# LR_EVM.net
KiCad netlist of a schematic drawn in Altium Designer
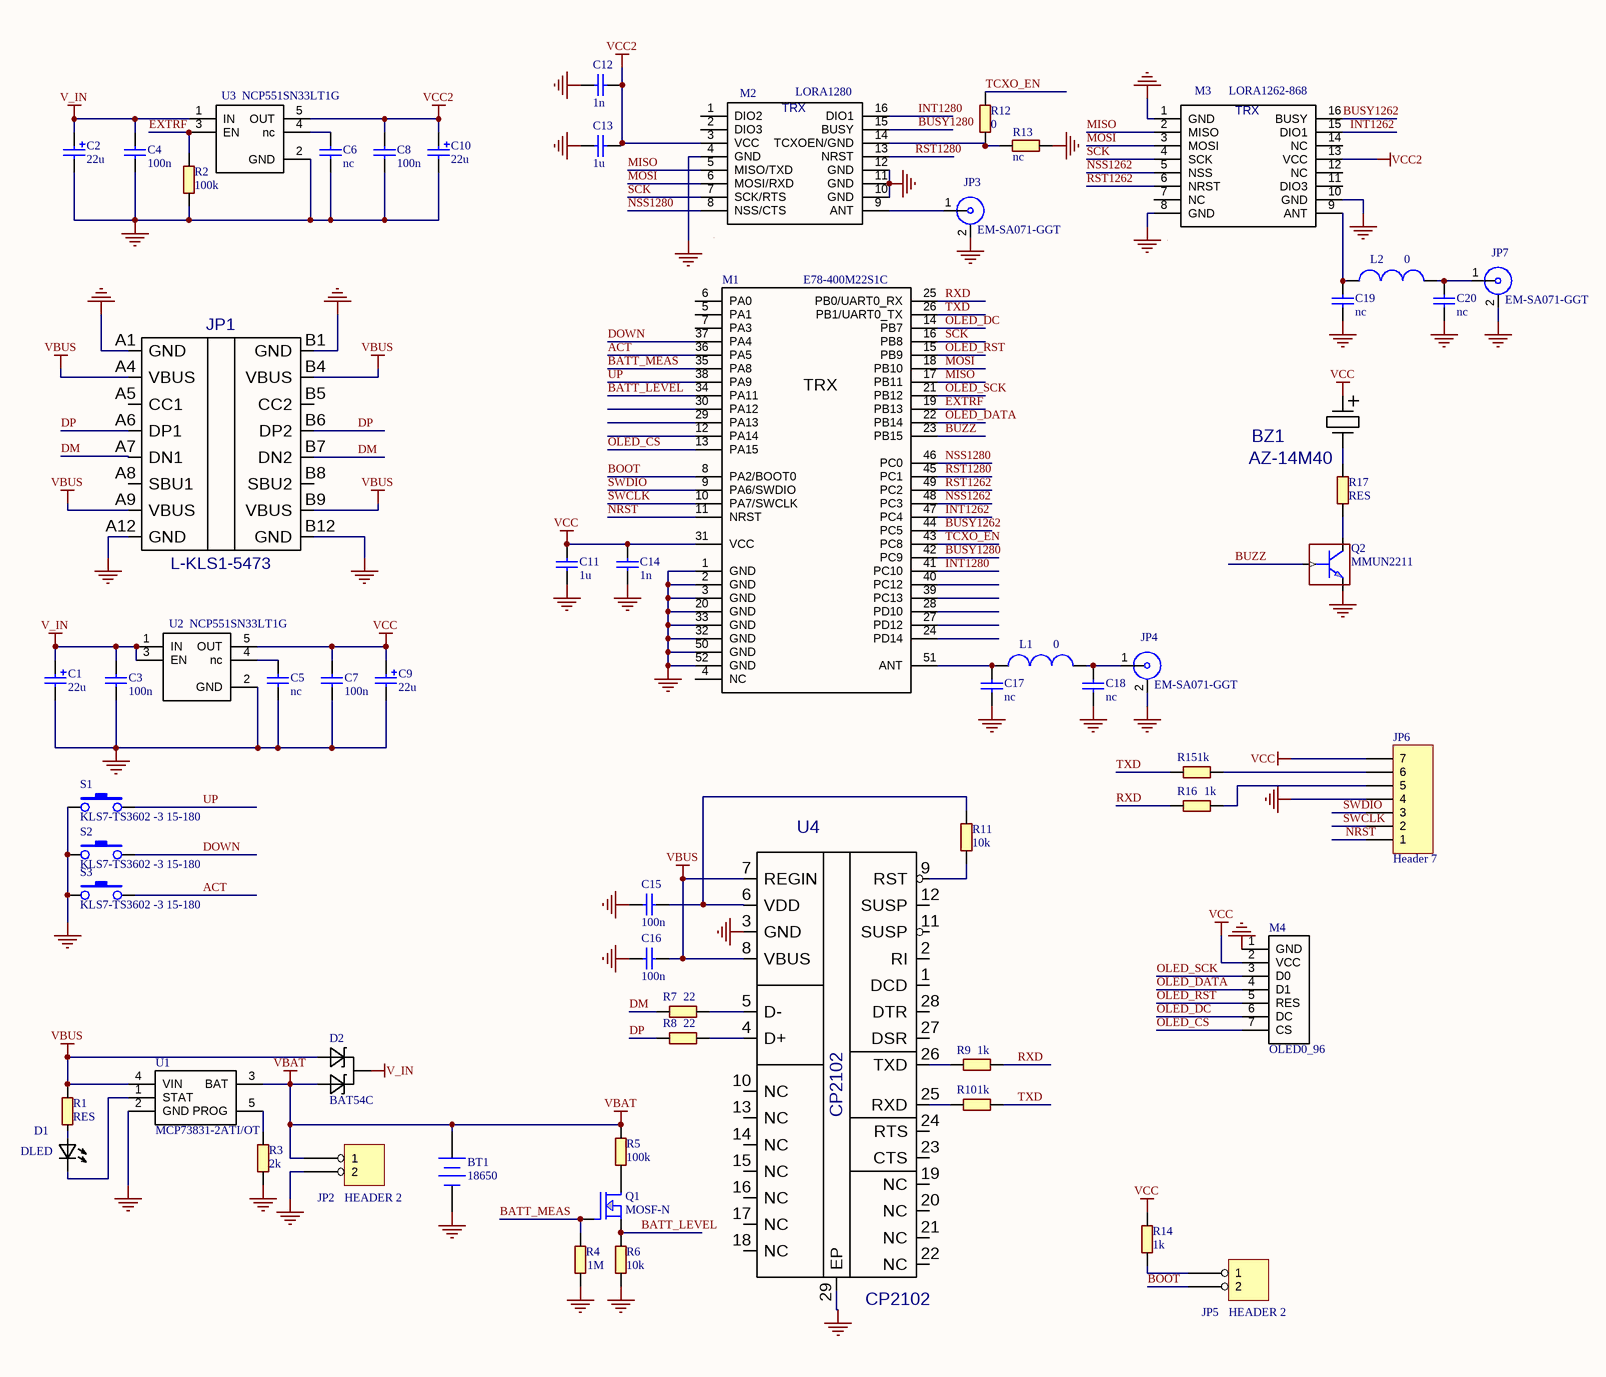
[diagram p0: LR_EVM.SchDoc]

(export (version "E")
  (design (tool "Eeschema 10.0.6"))
  (components
    (comp (ref "BT1")
      (value "18650")
      (footprint "18650")
      (description "Multicell Battery")
      (fields (field (name "PUBLISHER") "Altium Limited"))
      (libsource (lib "zucker") (part "Battery"))
    )
    (comp (ref "BZ1")
      (value "AZ-14M40")
      (footprint "AZ-14M40")
      (libsource (lib "zucker") (part "BUZ-AZ-14M40"))
    )
    (comp (ref "C1")
      (value "22u")
      (footprint "C_TANTAL_A")
      (fields (field (name "VOLTAGE") "16V"))
      (libsource (lib "Passive") (part "CAPP"))
    )
    (comp (ref "C2")
      (value "22u")
      (footprint "C_TANTAL_A")
      (fields (field (name "VOLTAGE") "16V"))
      (libsource (lib "Passive") (part "CAPP"))
    )
    (comp (ref "C3")
      (value "100n")
      (footprint "C-0603")
      (fields (field (name "VOLTAGE") "50V"))
      (libsource (lib "Passive") (part "CAPN"))
    )
    (comp (ref "C4")
      (value "100n")
      (footprint "C-0603")
      (fields (field (name "VOLTAGE") "50V"))
      (libsource (lib "Passive") (part "CAPN"))
    )
    (comp (ref "C5")
      (value "nc")
      (footprint "C-0603")
      (fields (field (name "VOLTAGE") "50V"))
      (libsource (lib "Passive") (part "CAPN"))
    )
    (comp (ref "C6")
      (value "nc")
      (footprint "C-0603")
      (fields (field (name "VOLTAGE") "50V"))
      (libsource (lib "Passive") (part "CAPN"))
    )
    (comp (ref "C7")
      (value "100n")
      (footprint "C-0603")
      (fields (field (name "VOLTAGE") "50V"))
      (libsource (lib "Passive") (part "CAPN"))
    )
    (comp (ref "C8")
      (value "100n")
      (footprint "C-0603")
      (fields (field (name "VOLTAGE") "50V"))
      (libsource (lib "Passive") (part "CAPN"))
    )
    (comp (ref "C9")
      (value "22u")
      (footprint "C_TANTAL_A")
      (fields (field (name "VOLTAGE") "16V"))
      (libsource (lib "Passive") (part "CAPP"))
    )
    (comp (ref "C10")
      (value "22u")
      (footprint "C_TANTAL_A")
      (fields (field (name "VOLTAGE") "16V"))
      (libsource (lib "Passive") (part "CAPP"))
    )
    (comp (ref "C11")
      (value "1u")
      (footprint "C-0603")
      (fields (field (name "VOLTAGE") "50V"))
      (libsource (lib "Passive") (part "CAPN"))
    )
    (comp (ref "C12")
      (value "1n")
      (footprint "C-0603")
      (fields (field (name "VOLTAGE") "50V"))
      (libsource (lib "Passive") (part "CAPN"))
    )
    (comp (ref "C13")
      (value "1u")
      (footprint "C-0603")
      (fields (field (name "VOLTAGE") "50V"))
      (libsource (lib "Passive") (part "CAPN"))
    )
    (comp (ref "C14")
      (value "1n")
      (footprint "C-0603")
      (fields (field (name "VOLTAGE") "50V"))
      (libsource (lib "Passive") (part "CAPN"))
    )
    (comp (ref "C15")
      (value "100n")
      (footprint "C-0603")
      (fields (field (name "VOLTAGE") "50V"))
      (libsource (lib "Passive") (part "CAPN"))
    )
    (comp (ref "C16")
      (value "100n")
      (footprint "C-0603")
      (fields (field (name "VOLTAGE") "50V"))
      (libsource (lib "Passive") (part "CAPN"))
    )
    (comp (ref "C17")
      (value "nc")
      (footprint "C-0603")
      (fields (field (name "VOLTAGE") "50V"))
      (libsource (lib "Passive") (part "CAPN"))
    )
    (comp (ref "C18")
      (value "nc")
      (footprint "C-0603")
      (fields (field (name "VOLTAGE") "50V"))
      (libsource (lib "Passive") (part "CAPN"))
    )
    (comp (ref "C19")
      (value "nc")
      (footprint "C-0603")
      (fields (field (name "VOLTAGE") "50V"))
      (libsource (lib "Passive") (part "CAPN"))
    )
    (comp (ref "C20")
      (value "nc")
      (footprint "C-0603")
      (fields (field (name "VOLTAGE") "50V"))
      (libsource (lib "Passive") (part "CAPN"))
    )
    (comp (ref "D1") (value "DLED") (footprint "LED_3mm_RED") (libsource (lib "zucker") (part "DLED")))
    (comp (ref "D2") (value "BAT54C") (footprint "SOT-23") (libsource (lib "zucker") (part "BAT54C")))
    (comp (ref "JP1")
      (value "L-KLS1-5473")
      (footprint "L-KLS1-5473")
      (libsource (lib "connectors") (part "L-KLS1-5473"))
    )
    (comp (ref "JP2")
      (value "HEADER 2")
      (footprint "PLS1-2")
      (libsource (lib "Connectors") (part "HEADER 2"))
    )
    (comp (ref "JP3")
      (value "EM-SA071-GGT")
      (footprint "SMA_F_EDGE")
      (description "SMA Female R/A PCB Mount")
      (libsource (lib "Connectors") (part "SMA"))
    )
    (comp (ref "JP4")
      (value "EM-SA071-GGT")
      (footprint "SMA_F_EDGE")
      (description "SMA Female R/A PCB Mount")
      (libsource (lib "Connectors") (part "SMA"))
    )
    (comp (ref "JP5")
      (value "HEADER 2")
      (footprint "PLS1-2")
      (libsource (lib "Connectors") (part "HEADER 2"))
    )
    (comp (ref "JP6")
      (value "Header 7")
      (footprint "PLS1-7R")
      (description "Header, 7-Pin")
      (fields (field (name "PUBLISHER") "Altium Limited"))
      (libsource (lib "Miscellaneous Connectors") (part "Header 7"))
    )
    (comp (ref "JP7")
      (value "EM-SA071-GGT")
      (footprint "SMA_F_EDGE")
      (description "SMA Female R/A PCB Mount")
      (libsource (lib "Connectors") (part "SMA"))
    )
    (comp (ref "L1") (value "0") (footprint "L-0603") (libsource (lib "Passive") (part "L")))
    (comp (ref "L2") (value "0") (footprint "L-0603") (libsource (lib "Passive") (part "L")))
    (comp (ref "M1")
      (value "E78-400M22S1C")
      (footprint "E78_400_M22S1C")
      (libsource (lib "zucker") (part "E78-400M22S1C"))
    )
    (comp (ref "M2")
      (value "LORA1280")
      (footprint "LGA16_LORA1280")
      (libsource (lib "RA08T") (part "LORA1280"))
    )
    (comp (ref "M3")
      (value "LORA1262-868")
      (footprint "LGA16_LORA1280")
      (libsource (lib "zucker") (part "LORA1262"))
    )
    (comp (ref "M4") (value "OLED0_96") (footprint "OLED096") (libsource (lib "zucker") (part "OLED0_96")))
    (comp (ref "Q1") (value "MOSF-N") (footprint "SOT-23") (libsource (lib "Transistors") (part "MOSF-N")))
    (comp (ref "Q2")
      (value "MMUN2211")
      (footprint "SOT-23")
      (libsource (lib "Transistors") (part "MMUN2211"))
    )
    (comp (ref "R1") (value "RES") (footprint "R-0603") (libsource (lib "") (part "RES_2")))
    (comp (ref "R2") (value "100k") (footprint "R-0603") (libsource (lib "") (part "RES_1")))
    (comp (ref "R3") (value "2k") (footprint "R-0603") (libsource (lib "") (part "RES_1")))
    (comp (ref "R4") (value "1M") (footprint "R-0603") (libsource (lib "") (part "RES_2")))
    (comp (ref "R5") (value "100k") (footprint "R-0603") (libsource (lib "") (part "RES_2")))
    (comp (ref "R6") (value "10k") (footprint "R-0603") (libsource (lib "") (part "RES_2")))
    (comp (ref "R7") (value "22") (footprint "R-0603") (libsource (lib "Passive") (part "RES")))
    (comp (ref "R8") (value "22") (footprint "R-0603") (libsource (lib "Passive") (part "RES")))
    (comp (ref "R9") (value "1k") (footprint "R-0603") (libsource (lib "Passive") (part "RES")))
    (comp (ref "R10") (value "1k") (footprint "R-0603") (libsource (lib "Passive") (part "RES")))
    (comp (ref "R11") (value "10k") (footprint "R-0603") (libsource (lib "") (part "RES_2")))
    (comp (ref "R12") (value "0") (footprint "R-0603") (libsource (lib "") (part "RES_1")))
    (comp (ref "R13") (value "nc") (footprint "R-0603") (libsource (lib "") (part "RES_3")))
    (comp (ref "R14") (value "1k") (footprint "R-0603") (libsource (lib "") (part "RES_2")))
    (comp (ref "R15") (value "1k") (footprint "R-0603") (libsource (lib "Passive") (part "RES")))
    (comp (ref "R16") (value "1k") (footprint "R-0603") (libsource (lib "Passive") (part "RES")))
    (comp (ref "R17") (value "RES") (footprint "R-0603") (libsource (lib "") (part "RES_2")))
    (comp (ref "S1")
      (value "KLS7-TS3602 -3 15-180")
      (footprint "KLS7-TS3602")
      (libsource (lib "Switches") (part "SW-1"))
    )
    (comp (ref "S2")
      (value "KLS7-TS3602 -3 15-180")
      (footprint "KLS7-TS3602")
      (libsource (lib "Switches") (part "SW-1"))
    )
    (comp (ref "S3")
      (value "KLS7-TS3602 -3 15-180")
      (footprint "KLS7-TS3602")
      (libsource (lib "Switches") (part "SW-1"))
    )
    (comp (ref "U1")
      (value "MCP73831-2ATI/OT")
      (footprint "SOT-23-5")
      (libsource (lib "zucker") (part "MCP73831"))
    )
    (comp (ref "U2")
      (value "NCP551SN33LT1G")
      (footprint "SOT-23-5")
      (description "50mA Low-Dropout Regulator")
      (libsource (lib "zucker") (part "LP2980"))
    )
    (comp (ref "U3")
      (value "NCP551SN33LT1G")
      (footprint "SOT-23-5")
      (description "50mA Low-Dropout Regulator")
      (libsource (lib "zucker") (part "LP2980"))
    )
    (comp (ref "U4") (value "CP2102") (footprint "QFN28") (libsource (lib "E2002") (part "CP2102")))
  )
  (nets
    (net (code "1") (name "/ACT") (class "Default")
      (node (ref "M1") (pin "36") (pinfunction "PA5_36") (pintype "passive"))
      (node (ref "S3") (pin "2") (pinfunction "2_2") (pintype "passive"))
    )
    (net (code "2") (name "/BATT_LEVEL") (class "Default")
      (node (ref "M1") (pin "34") (pinfunction "PA11_34") (pintype "passive"))
      (node (ref "Q1") (pin "2") (pinfunction "SOURCE_2") (pintype "passive"))
      (node (ref "R6") (pin "1") (pinfunction "1_1") (pintype "passive"))
    )
    (net (code "3") (name "/BATT_MEAS") (class "Default")
      (node (ref "M1") (pin "35") (pinfunction "PA8_35") (pintype "passive"))
      (node (ref "Q1") (pin "1") (pinfunction "GATE_1") (pintype "passive"))
      (node (ref "R4") (pin "1") (pinfunction "1_1") (pintype "passive"))
    )
    (net (code "4") (name "/BOOT") (class "Default")
      (node (ref "JP5") (pin "2") (pinfunction "2_2") (pintype "passive"))
      (node (ref "M1") (pin "8") (pinfunction "PA2/BOOT0_8") (pintype "passive"))
    )
    (net (code "5") (name "/BUSY1262") (class "Default")
      (node (ref "M1") (pin "44") (pinfunction "PC5_44") (pintype "passive"))
      (node (ref "M3") (pin "16") (pinfunction "BUSY_16") (pintype "passive"))
    )
    (net (code "6") (name "/BUSY1280") (class "Default")
      (node (ref "M1") (pin "42") (pinfunction "PC9_42") (pintype "passive"))
      (node (ref "M2") (pin "15") (pinfunction "BUSY_15") (pintype "passive"))
    )
    (net (code "7") (name "/BUZZ") (class "Default")
      (node (ref "M1") (pin "23") (pinfunction "PB15_23") (pintype "passive"))
      (node (ref "Q2") (pin "1") (pinfunction "BASE_1") (pintype "input"))
    )
    (net (code "8") (name "/DM") (class "Default")
      (node (ref "JP1") (pin "A7") (pinfunction "DN1_A7") (pintype "passive"))
      (node (ref "JP1") (pin "B7") (pinfunction "DN2_B7") (pintype "passive"))
      (node (ref "R7") (pin "2") (pinfunction "2_2") (pintype "passive"))
    )
    (net (code "9") (name "/DOWN") (class "Default")
      (node (ref "M1") (pin "37") (pinfunction "PA4_37") (pintype "passive"))
      (node (ref "S2") (pin "2") (pinfunction "2_2") (pintype "passive"))
    )
    (net (code "10") (name "/DP") (class "Default")
      (node (ref "JP1") (pin "A6") (pinfunction "DP1_A6") (pintype "passive"))
      (node (ref "JP1") (pin "B6") (pinfunction "DP2_B6") (pintype "passive"))
      (node (ref "R8") (pin "2") (pinfunction "2_2") (pintype "passive"))
    )
    (net (code "11") (name "/EXTRF") (class "Default")
      (node (ref "M1") (pin "19") (pinfunction "PB13_19") (pintype "passive"))
      (node (ref "R2") (pin "2") (pinfunction "2_2") (pintype "passive"))
      (node (ref "U3") (pin "3") (pinfunction "EN_3") (pintype "passive"))
    )
    (net (code "12") (name "/INT1262") (class "Default")
      (node (ref "M1") (pin "47") (pinfunction "PC4_47") (pintype "passive"))
      (node (ref "M3") (pin "15") (pinfunction "DIO1_15") (pintype "passive"))
    )
    (net (code "13") (name "/INT1280") (class "Default")
      (node (ref "M1") (pin "41") (pinfunction "PC10_41") (pintype "passive"))
      (node (ref "M2") (pin "16") (pinfunction "DIO1_16") (pintype "passive"))
    )
    (net (code "14") (name "/MISO") (class "Default")
      (node (ref "M1") (pin "17") (pinfunction "PB11_17") (pintype "passive"))
      (node (ref "M2") (pin "5") (pinfunction "MISO/TXD_5") (pintype "passive"))
      (node (ref "M3") (pin "2") (pinfunction "MISO_2") (pintype "passive"))
    )
    (net (code "15") (name "/MOSI") (class "Default")
      (node (ref "M1") (pin "18") (pinfunction "PB10_18") (pintype "passive"))
      (node (ref "M2") (pin "6") (pinfunction "MOSI/RXD_6") (pintype "passive"))
      (node (ref "M3") (pin "3") (pinfunction "MOSI_3") (pintype "passive"))
    )
    (net (code "16") (name "/NRST") (class "Default")
      (node (ref "JP6") (pin "1") (pinfunction "1_1") (pintype "passive"))
      (node (ref "M1") (pin "11") (pinfunction "NRST_11") (pintype "passive"))
    )
    (net (code "17") (name "/NSS1262") (class "Default")
      (node (ref "M1") (pin "48") (pinfunction "PC3_48") (pintype "passive"))
      (node (ref "M3") (pin "5") (pinfunction "NSS_5") (pintype "passive"))
    )
    (net (code "18") (name "/NSS1280") (class "Default")
      (node (ref "M1") (pin "46") (pinfunction "PC0_46") (pintype "passive"))
      (node (ref "M2") (pin "8") (pinfunction "NSS/CTS_8") (pintype "passive"))
    )
    (net (code "19") (name "/OLED_CS") (class "Default")
      (node (ref "M1") (pin "13") (pinfunction "PA15_13") (pintype "passive"))
      (node (ref "M4") (pin "7") (pinfunction "CS_7") (pintype "passive"))
    )
    (net (code "20") (name "/OLED_DATA") (class "Default")
      (node (ref "M1") (pin "22") (pinfunction "PB14_22") (pintype "passive"))
      (node (ref "M4") (pin "4") (pinfunction "D1_4") (pintype "passive"))
    )
    (net (code "21") (name "/OLED_DC") (class "Default")
      (node (ref "M1") (pin "14") (pinfunction "PB7_14") (pintype "passive"))
      (node (ref "M4") (pin "6") (pinfunction "DC_6") (pintype "passive"))
    )
    (net (code "22") (name "/OLED_RST") (class "Default")
      (node (ref "M1") (pin "15") (pinfunction "PB9_15") (pintype "passive"))
      (node (ref "M4") (pin "5") (pinfunction "RES_5") (pintype "passive"))
    )
    (net (code "23") (name "/OLED_SCK") (class "Default")
      (node (ref "M1") (pin "21") (pinfunction "PB12_21") (pintype "passive"))
      (node (ref "M4") (pin "3") (pinfunction "D0_3") (pintype "passive"))
    )
    (net (code "24") (name "/RST1262") (class "Default")
      (node (ref "M1") (pin "49") (pinfunction "PC2_49") (pintype "passive"))
      (node (ref "M3") (pin "6") (pinfunction "NRST_6") (pintype "passive"))
    )
    (net (code "25") (name "/RST1280") (class "Default")
      (node (ref "M1") (pin "45") (pinfunction "PC1_45") (pintype "passive"))
      (node (ref "M2") (pin "13") (pinfunction "NRST_13") (pintype "passive"))
    )
    (net (code "26") (name "/RXD") (class "Default")
      (node (ref "M1") (pin "25") (pinfunction "PB0/UART0_RX_25") (pintype "passive"))
      (node (ref "R16") (pin "2") (pinfunction "2_2") (pintype "passive"))
      (node (ref "R9") (pin "1") (pinfunction "1_1") (pintype "passive"))
    )
    (net (code "27") (name "/SCK") (class "Default")
      (node (ref "M1") (pin "16") (pinfunction "PB8_16") (pintype "passive"))
      (node (ref "M2") (pin "7") (pinfunction "SCK/RTS_7") (pintype "passive"))
      (node (ref "M3") (pin "4") (pinfunction "SCK_4") (pintype "passive"))
    )
    (net (code "28") (name "/SWCLK") (class "Default")
      (node (ref "JP6") (pin "2") (pinfunction "2_2") (pintype "passive"))
      (node (ref "M1") (pin "10") (pinfunction "PA7/SWCLK_10") (pintype "passive"))
    )
    (net (code "29") (name "/SWDIO") (class "Default")
      (node (ref "JP6") (pin "3") (pinfunction "3_3") (pintype "passive"))
      (node (ref "M1") (pin "9") (pinfunction "PA6/SWDIO_9") (pintype "passive"))
    )
    (net (code "30") (name "/TCXO_EN") (class "Default")
      (node (ref "M1") (pin "43") (pinfunction "PC8_43") (pintype "passive"))
      (node (ref "R12") (pin "2") (pinfunction "2_2") (pintype "passive"))
    )
    (net (code "31") (name "/TXD") (class "Default")
      (node (ref "M1") (pin "26") (pinfunction "PB1/UART0_TX_26") (pintype "passive"))
      (node (ref "R10") (pin "1") (pinfunction "1_1") (pintype "passive"))
      (node (ref "R15") (pin "2") (pinfunction "2_2") (pintype "passive"))
    )
    (net (code "32") (name "/UP") (class "Default")
      (node (ref "M1") (pin "38") (pinfunction "PA9_38") (pintype "passive"))
      (node (ref "S1") (pin "2") (pinfunction "2_2") (pintype "passive"))
    )
    (net (code "33") (name "GND") (class "Default")
      (node (ref "BT1") (pin "2") (pinfunction "-_2") (pintype "passive"))
      (node (ref "C1") (pin "1") (pinfunction "1_1") (pintype "passive"))
      (node (ref "C10") (pin "1") (pinfunction "1_1") (pintype "passive"))
      (node (ref "C11") (pin "2") (pinfunction "2_2") (pintype "passive"))
      (node (ref "C12") (pin "2") (pinfunction "2_2") (pintype "passive"))
      (node (ref "C13") (pin "2") (pinfunction "2_2") (pintype "passive"))
      (node (ref "C14") (pin "2") (pinfunction "2_2") (pintype "passive"))
      (node (ref "C15") (pin "2") (pinfunction "2_2") (pintype "passive"))
      (node (ref "C16") (pin "1") (pinfunction "1_1") (pintype "passive"))
      (node (ref "C17") (pin "2") (pinfunction "2_2") (pintype "passive"))
      (node (ref "C18") (pin "2") (pinfunction "2_2") (pintype "passive"))
      (node (ref "C19") (pin "2") (pinfunction "2_2") (pintype "passive"))
      (node (ref "C2") (pin "1") (pinfunction "1_1") (pintype "passive"))
      (node (ref "C20") (pin "2") (pinfunction "2_2") (pintype "passive"))
      (node (ref "C3") (pin "2") (pinfunction "2_2") (pintype "passive"))
      (node (ref "C4") (pin "2") (pinfunction "2_2") (pintype "passive"))
      (node (ref "C5") (pin "2") (pinfunction "2_2") (pintype "passive"))
      (node (ref "C6") (pin "2") (pinfunction "2_2") (pintype "passive"))
      (node (ref "C7") (pin "2") (pinfunction "2_2") (pintype "passive"))
      (node (ref "C8") (pin "2") (pinfunction "2_2") (pintype "passive"))
      (node (ref "C9") (pin "1") (pinfunction "1_1") (pintype "passive"))
      (node (ref "JP1") (pin "A1") (pinfunction "GND_A1") (pintype "passive"))
      (node (ref "JP1") (pin "A12") (pinfunction "GND_A12") (pintype "passive"))
      (node (ref "JP1") (pin "B1") (pinfunction "GND_B1") (pintype "passive"))
      (node (ref "JP1") (pin "B12") (pinfunction "GND_B12") (pintype "passive"))
      (node (ref "JP2") (pin "2") (pinfunction "2_2") (pintype "passive"))
      (node (ref "JP3") (pin "2") (pinfunction "2_2") (pintype "passive"))
      (node (ref "JP4") (pin "2") (pinfunction "2_2") (pintype "passive"))
      (node (ref "JP6") (pin "4") (pinfunction "4_4") (pintype "passive"))
      (node (ref "JP7") (pin "2") (pinfunction "2_2") (pintype "passive"))
      (node (ref "M1") (pin "1") (pinfunction "GND_1") (pintype "passive"))
      (node (ref "M1") (pin "2") (pinfunction "GND_2") (pintype "passive"))
      (node (ref "M1") (pin "20") (pinfunction "GND_20") (pintype "passive"))
      (node (ref "M1") (pin "3") (pinfunction "GND_3") (pintype "passive"))
      (node (ref "M1") (pin "32") (pinfunction "GND_32") (pintype "passive"))
      (node (ref "M1") (pin "33") (pinfunction "GND_33") (pintype "passive"))
      (node (ref "M1") (pin "50") (pinfunction "GND_50") (pintype "passive"))
      (node (ref "M1") (pin "52") (pinfunction "GND_52") (pintype "passive"))
      (node (ref "M2") (pin "10") (pinfunction "GND_10") (pintype "passive"))
      (node (ref "M2") (pin "11") (pinfunction "GND_11") (pintype "passive"))
      (node (ref "M2") (pin "12") (pinfunction "GND_12") (pintype "passive"))
      (node (ref "M2") (pin "4") (pinfunction "GND_4") (pintype "passive"))
      (node (ref "M3") (pin "1") (pinfunction "GND_1") (pintype "passive"))
      (node (ref "M3") (pin "10") (pinfunction "GND_10") (pintype "passive"))
      (node (ref "M3") (pin "8") (pinfunction "GND_8") (pintype "passive"))
      (node (ref "M4") (pin "1") (pinfunction "GND_1") (pintype "passive"))
      (node (ref "Q2") (pin "2") (pinfunction "EMITTER_2") (pintype "passive"))
      (node (ref "R13") (pin "2") (pinfunction "2_2") (pintype "passive"))
      (node (ref "R2") (pin "1") (pinfunction "1_1") (pintype "passive"))
      (node (ref "R3") (pin "1") (pinfunction "1_1") (pintype "passive"))
      (node (ref "R4") (pin "2") (pinfunction "2_2") (pintype "passive"))
      (node (ref "R6") (pin "2") (pinfunction "2_2") (pintype "passive"))
      (node (ref "S1") (pin "1") (pinfunction "1_1") (pintype "passive"))
      (node (ref "S2") (pin "1") (pinfunction "1_1") (pintype "passive"))
      (node (ref "S3") (pin "1") (pinfunction "1_1") (pintype "passive"))
      (node (ref "U1") (pin "2") (pinfunction "GND_2") (pintype "passive"))
      (node (ref "U2") (pin "2") (pinfunction "GND_2") (pintype "passive"))
      (node (ref "U3") (pin "2") (pinfunction "GND_2") (pintype "passive"))
      (node (ref "U4") (pin "29") (pinfunction "EP_29") (pintype "passive"))
      (node (ref "U4") (pin "3") (pinfunction "GND_3") (pintype "passive"))
    )
    (net (code "34") (name "Net-(BZ1-Pad2)") (class "Default")
      (node (ref "BZ1") (pin "2") (pinfunction "2_2") (pintype "passive"))
      (node (ref "R17") (pin "1") (pinfunction "1_1") (pintype "passive"))
    )
    (net (code "35") (name "Net-(C18-Pad1)") (class "Default")
      (node (ref "C18") (pin "1") (pinfunction "1_1") (pintype "passive"))
      (node (ref "JP4") (pin "1") (pinfunction "1_1") (pintype "passive"))
      (node (ref "L1") (pin "2") (pinfunction "2_2") (pintype "passive"))
    )
    (net (code "36") (name "Net-(C20-Pad1)") (class "Default")
      (node (ref "C20") (pin "1") (pinfunction "1_1") (pintype "passive"))
      (node (ref "JP7") (pin "1") (pinfunction "1_1") (pintype "passive"))
      (node (ref "L2") (pin "2") (pinfunction "2_2") (pintype "passive"))
    )
    (net (code "37") (name "Net-(D1-Pad1)") (class "Default")
      (node (ref "D1") (pin "1") (pinfunction "1_1") (pintype "passive"))
      (node (ref "R1") (pin "2") (pinfunction "2_2") (pintype "passive"))
    )
    (net (code "38") (name "Net-(JP5-Pad1)") (class "Default")
      (node (ref "JP5") (pin "1") (pinfunction "1_1") (pintype "passive"))
      (node (ref "R14") (pin "2") (pinfunction "2_2") (pintype "passive"))
    )
    (net (code "39") (name "Net-(JP6-Pad5)") (class "Default")
      (node (ref "JP6") (pin "5") (pinfunction "5_5") (pintype "passive"))
      (node (ref "R16") (pin "1") (pinfunction "1_1") (pintype "passive"))
    )
    (net (code "40") (name "Net-(JP6-Pad6)") (class "Default")
      (node (ref "JP6") (pin "6") (pinfunction "6_6") (pintype "passive"))
      (node (ref "R15") (pin "1") (pinfunction "1_1") (pintype "passive"))
    )
    (net (code "41") (name "Net-(M1-ANT)") (class "Default")
      (node (ref "C17") (pin "1") (pinfunction "1_1") (pintype "passive"))
      (node (ref "L1") (pin "1") (pinfunction "1_1") (pintype "passive"))
      (node (ref "M1") (pin "51") (pinfunction "ANT_51") (pintype "passive"))
    )
    (net (code "42") (name "Net-(M2-ANT)") (class "Default")
      (node (ref "JP3") (pin "1") (pinfunction "1_1") (pintype "passive"))
      (node (ref "M2") (pin "9") (pinfunction "ANT_9") (pintype "passive"))
    )
    (net (code "43") (name "Net-(M2-TCXOEN{slash}GND)") (class "Default")
      (node (ref "M2") (pin "14") (pinfunction "TCXOEN/GND_14") (pintype "passive"))
      (node (ref "R12") (pin "1") (pinfunction "1_1") (pintype "passive"))
      (node (ref "R13") (pin "1") (pinfunction "1_1") (pintype "passive"))
    )
    (net (code "44") (name "Net-(M3-ANT)") (class "Default")
      (node (ref "C19") (pin "1") (pinfunction "1_1") (pintype "passive"))
      (node (ref "L2") (pin "1") (pinfunction "1_1") (pintype "passive"))
      (node (ref "M3") (pin "9") (pinfunction "ANT_9") (pintype "passive"))
    )
    (net (code "45") (name "Net-(Q1-DRAIN)") (class "Default")
      (node (ref "Q1") (pin "3") (pinfunction "DRAIN_3") (pintype "passive"))
      (node (ref "R5") (pin "2") (pinfunction "2_2") (pintype "passive"))
    )
    (net (code "46") (name "Net-(Q2-COLLECTOR)") (class "Default")
      (node (ref "Q2") (pin "3") (pinfunction "COLLECTOR_3") (pintype "passive"))
      (node (ref "R17") (pin "2") (pinfunction "2_2") (pintype "passive"))
    )
    (net (code "47") (name "Net-(U1-PROG)") (class "Default")
      (node (ref "R3") (pin "2") (pinfunction "2_2") (pintype "passive"))
      (node (ref "U1") (pin "5") (pinfunction "PROG_5") (pintype "passive"))
    )
    (net (code "48") (name "Net-(U1-STAT)") (class "Default")
      (node (ref "D1") (pin "2") (pinfunction "2_2") (pintype "passive"))
      (node (ref "U1") (pin "1") (pinfunction "STAT_1") (pintype "passive"))
    )
    (net (code "49") (name "Net-(U2-nc)") (class "Default")
      (node (ref "C5") (pin "1") (pinfunction "1_1") (pintype "passive"))
      (node (ref "U2") (pin "4") (pinfunction "nc_4") (pintype "passive"))
    )
    (net (code "50") (name "Net-(U3-nc)") (class "Default")
      (node (ref "C6") (pin "1") (pinfunction "1_1") (pintype "passive"))
      (node (ref "U3") (pin "4") (pinfunction "nc_4") (pintype "passive"))
    )
    (net (code "51") (name "Net-(U4-D+)") (class "Default")
      (node (ref "R8") (pin "1") (pinfunction "1_1") (pintype "passive"))
      (node (ref "U4") (pin "4") (pinfunction "D+_4") (pintype "passive"))
    )
    (net (code "52") (name "Net-(U4-D-)") (class "Default")
      (node (ref "R7") (pin "1") (pinfunction "1_1") (pintype "passive"))
      (node (ref "U4") (pin "5") (pinfunction "D-_5") (pintype "passive"))
    )
    (net (code "53") (name "Net-(U4-RST)") (class "Default")
      (node (ref "R11") (pin "2") (pinfunction "2_2") (pintype "passive"))
      (node (ref "U4") (pin "9") (pinfunction "RST_9") (pintype "passive"))
    )
    (net (code "54") (name "Net-(U4-RXD)") (class "Default")
      (node (ref "R10") (pin "2") (pinfunction "2_2") (pintype "passive"))
      (node (ref "U4") (pin "25") (pinfunction "RXD_25") (pintype "passive"))
    )
    (net (code "55") (name "Net-(U4-TXD)") (class "Default")
      (node (ref "R9") (pin "2") (pinfunction "2_2") (pintype "passive"))
      (node (ref "U4") (pin "26") (pinfunction "TXD_26") (pintype "passive"))
    )
    (net (code "56") (name "Net-(U4-VDD)") (class "Default")
      (node (ref "C15") (pin "1") (pinfunction "1_1") (pintype "passive"))
      (node (ref "R11") (pin "1") (pinfunction "1_1") (pintype "passive"))
      (node (ref "U4") (pin "6") (pinfunction "VDD_6") (pintype "passive"))
    )
    (net (code "57") (name "VBAT") (class "Default")
      (node (ref "BT1") (pin "1") (pinfunction "+_1") (pintype "passive"))
      (node (ref "D2") (pin "1") (pinfunction "A1_1") (pintype "passive"))
      (node (ref "JP2") (pin "1") (pinfunction "1_1") (pintype "passive"))
      (node (ref "R5") (pin "1") (pinfunction "1_1") (pintype "passive"))
      (node (ref "U1") (pin "3") (pinfunction "BAT_3") (pintype "passive"))
    )
    (net (code "58") (name "VBUS") (class "Default")
      (node (ref "C16") (pin "2") (pinfunction "2_2") (pintype "passive"))
      (node (ref "D2") (pin "2") (pinfunction "A2_2") (pintype "passive"))
      (node (ref "JP1") (pin "A4") (pinfunction "VBUS_A4") (pintype "passive"))
      (node (ref "JP1") (pin "A9") (pinfunction "VBUS_A9") (pintype "passive"))
      (node (ref "JP1") (pin "B4") (pinfunction "VBUS_B4") (pintype "passive"))
      (node (ref "JP1") (pin "B9") (pinfunction "VBUS_B9") (pintype "passive"))
      (node (ref "R1") (pin "1") (pinfunction "1_1") (pintype "passive"))
      (node (ref "U1") (pin "4") (pinfunction "VIN_4") (pintype "passive"))
      (node (ref "U4") (pin "7") (pinfunction "REGIN_7") (pintype "passive"))
      (node (ref "U4") (pin "8") (pinfunction "VBUS_8") (pintype "passive"))
    )
    (net (code "59") (name "VCC") (class "Default")
      (node (ref "BZ1") (pin "1") (pinfunction "1_1") (pintype "passive"))
      (node (ref "C11") (pin "1") (pinfunction "1_1") (pintype "passive"))
      (node (ref "C14") (pin "1") (pinfunction "1_1") (pintype "passive"))
      (node (ref "C7") (pin "1") (pinfunction "1_1") (pintype "passive"))
      (node (ref "C9") (pin "2") (pinfunction "2_2") (pintype "passive"))
      (node (ref "JP6") (pin "7") (pinfunction "7_7") (pintype "passive"))
      (node (ref "M1") (pin "31") (pinfunction "VCC_31") (pintype "passive"))
      (node (ref "M4") (pin "2") (pinfunction "VCC_2") (pintype "passive"))
      (node (ref "R14") (pin "1") (pinfunction "1_1") (pintype "passive"))
      (node (ref "U2") (pin "5") (pinfunction "OUT_5") (pintype "passive"))
    )
    (net (code "60") (name "VCC2") (class "Default")
      (node (ref "C10") (pin "2") (pinfunction "2_2") (pintype "passive"))
      (node (ref "C12") (pin "1") (pinfunction "1_1") (pintype "passive"))
      (node (ref "C13") (pin "1") (pinfunction "1_1") (pintype "passive"))
      (node (ref "C8") (pin "1") (pinfunction "1_1") (pintype "passive"))
      (node (ref "M2") (pin "3") (pinfunction "VCC_3") (pintype "passive"))
      (node (ref "M3") (pin "13") (pinfunction "VCC_13") (pintype "passive"))
      (node (ref "U3") (pin "5") (pinfunction "OUT_5") (pintype "passive"))
    )
    (net (code "61") (name "VSS") (class "Default")
      (node (ref "JP1") (pin "17") (pinfunction "VSS_17") (pintype "power_in"))
    )
    (net (code "62") (name "V_IN") (class "Default")
      (node (ref "C1") (pin "2") (pinfunction "2_2") (pintype "passive"))
      (node (ref "C2") (pin "2") (pinfunction "2_2") (pintype "passive"))
      (node (ref "C3") (pin "1") (pinfunction "1_1") (pintype "passive"))
      (node (ref "C4") (pin "1") (pinfunction "1_1") (pintype "passive"))
      (node (ref "D2") (pin "3") (pinfunction "C1C2_3") (pintype "passive"))
      (node (ref "U2") (pin "1") (pinfunction "IN_1") (pintype "passive"))
      (node (ref "U2") (pin "3") (pinfunction "EN_3") (pintype "passive"))
      (node (ref "U3") (pin "1") (pinfunction "IN_1") (pintype "passive"))
    )
    (net (code "63") (name "unconnected-(JP1-CC1-PadA5)") (class "Default")
      (node (ref "JP1") (pin "A5") (pinfunction "CC1_A5") (pintype "passive"))
    )
    (net (code "64") (name "unconnected-(JP1-CC2-PadB5)") (class "Default")
      (node (ref "JP1") (pin "B5") (pinfunction "CC2_B5") (pintype "passive"))
    )
    (net (code "65") (name "unconnected-(JP1-SBU1-PadA8)") (class "Default")
      (node (ref "JP1") (pin "A8") (pinfunction "SBU1_A8") (pintype "passive"))
    )
    (net (code "66") (name "unconnected-(JP1-SBU2-PadB8)") (class "Default")
      (node (ref "JP1") (pin "B8") (pinfunction "SBU2_B8") (pintype "passive"))
    )
    (net (code "67") (name "unconnected-(M1-NC-Pad4)") (class "Default")
      (node (ref "M1") (pin "4") (pinfunction "NC_4") (pintype "passive"))
    )
    (net (code "68") (name "unconnected-(M1-PA0-Pad6)") (class "Default")
      (node (ref "M1") (pin "6") (pinfunction "PA0_6") (pintype "passive"))
    )
    (net (code "69") (name "unconnected-(M1-PA1-Pad5)") (class "Default")
      (node (ref "M1") (pin "5") (pinfunction "PA1_5") (pintype "passive"))
    )
    (net (code "70") (name "unconnected-(M1-PA3-Pad7)") (class "Default")
      (node (ref "M1") (pin "7") (pinfunction "PA3_7") (pintype "passive"))
    )
    (net (code "71") (name "unconnected-(M1-PA12-Pad30)") (class "Default")
      (node (ref "M1") (pin "30") (pinfunction "PA12_30") (pintype "passive"))
    )
    (net (code "72") (name "unconnected-(M1-PA13-Pad29)") (class "Default")
      (node (ref "M1") (pin "29") (pinfunction "PA13_29") (pintype "passive"))
    )
    (net (code "73") (name "unconnected-(M1-PA14-Pad12)") (class "Default")
      (node (ref "M1") (pin "12") (pinfunction "PA14_12") (pintype "passive"))
    )
    (net (code "74") (name "unconnected-(M1-PC12-Pad40)") (class "Default")
      (node (ref "M1") (pin "40") (pinfunction "PC12_40") (pintype "passive"))
    )
    (net (code "75") (name "unconnected-(M1-PC13-Pad39)") (class "Default")
      (node (ref "M1") (pin "39") (pinfunction "PC13_39") (pintype "passive"))
    )
    (net (code "76") (name "unconnected-(M1-PD10-Pad28)") (class "Default")
      (node (ref "M1") (pin "28") (pinfunction "PD10_28") (pintype "passive"))
    )
    (net (code "77") (name "unconnected-(M1-PD12-Pad27)") (class "Default")
      (node (ref "M1") (pin "27") (pinfunction "PD12_27") (pintype "passive"))
    )
    (net (code "78") (name "unconnected-(M1-PD14-Pad24)") (class "Default")
      (node (ref "M1") (pin "24") (pinfunction "PD14_24") (pintype "passive"))
    )
    (net (code "79") (name "unconnected-(M2-DIO2-Pad1)") (class "Default")
      (node (ref "M2") (pin "1") (pinfunction "DIO2_1") (pintype "passive"))
    )
    (net (code "80") (name "unconnected-(M2-DIO3-Pad2)") (class "Default")
      (node (ref "M2") (pin "2") (pinfunction "DIO3_2") (pintype "passive"))
    )
    (net (code "81") (name "unconnected-(M3-DIO3-Pad11)") (class "Default")
      (node (ref "M3") (pin "11") (pinfunction "DIO3_11") (pintype "passive"))
    )
    (net (code "82") (name "unconnected-(M3-NC-Pad7)") (class "Default")
      (node (ref "M3") (pin "7") (pinfunction "NC_7") (pintype "passive"))
    )
    (net (code "83") (name "unconnected-(M3-NC-Pad12)") (class "Default")
      (node (ref "M3") (pin "12") (pinfunction "NC_12") (pintype "passive"))
    )
    (net (code "84") (name "unconnected-(M3-NC-Pad14)") (class "Default")
      (node (ref "M3") (pin "14") (pinfunction "NC_14") (pintype "passive"))
    )
    (net (code "85") (name "unconnected-(U4-CTS-Pad23)") (class "Default")
      (node (ref "U4") (pin "23") (pinfunction "CTS_23") (pintype "passive"))
    )
    (net (code "86") (name "unconnected-(U4-DCD-Pad1)") (class "Default")
      (node (ref "U4") (pin "1") (pinfunction "DCD_1") (pintype "passive"))
    )
    (net (code "87") (name "unconnected-(U4-DSR-Pad27)") (class "Default")
      (node (ref "U4") (pin "27") (pinfunction "DSR_27") (pintype "passive"))
    )
    (net (code "88") (name "unconnected-(U4-DTR-Pad28)") (class "Default")
      (node (ref "U4") (pin "28") (pinfunction "DTR_28") (pintype "passive"))
    )
    (net (code "89") (name "unconnected-(U4-NC-Pad10)") (class "Default")
      (node (ref "U4") (pin "10") (pinfunction "NC_10") (pintype "passive"))
    )
    (net (code "90") (name "unconnected-(U4-NC-Pad13)") (class "Default")
      (node (ref "U4") (pin "13") (pinfunction "NC_13") (pintype "passive"))
    )
    (net (code "91") (name "unconnected-(U4-NC-Pad14)") (class "Default")
      (node (ref "U4") (pin "14") (pinfunction "NC_14") (pintype "passive"))
    )
    (net (code "92") (name "unconnected-(U4-NC-Pad15)") (class "Default")
      (node (ref "U4") (pin "15") (pinfunction "NC_15") (pintype "passive"))
    )
    (net (code "93") (name "unconnected-(U4-NC-Pad16)") (class "Default")
      (node (ref "U4") (pin "16") (pinfunction "NC_16") (pintype "passive"))
    )
    (net (code "94") (name "unconnected-(U4-NC-Pad17)") (class "Default")
      (node (ref "U4") (pin "17") (pinfunction "NC_17") (pintype "passive"))
    )
    (net (code "95") (name "unconnected-(U4-NC-Pad18)") (class "Default")
      (node (ref "U4") (pin "18") (pinfunction "NC_18") (pintype "passive"))
    )
    (net (code "96") (name "unconnected-(U4-NC-Pad19)") (class "Default")
      (node (ref "U4") (pin "19") (pinfunction "NC_19") (pintype "passive"))
    )
    (net (code "97") (name "unconnected-(U4-NC-Pad20)") (class "Default")
      (node (ref "U4") (pin "20") (pinfunction "NC_20") (pintype "passive"))
    )
    (net (code "98") (name "unconnected-(U4-NC-Pad21)") (class "Default")
      (node (ref "U4") (pin "21") (pinfunction "NC_21") (pintype "passive"))
    )
    (net (code "99") (name "unconnected-(U4-NC-Pad22)") (class "Default")
      (node (ref "U4") (pin "22") (pinfunction "NC_22") (pintype "passive"))
    )
    (net (code "100") (name "unconnected-(U4-RI-Pad2)") (class "Default")
      (node (ref "U4") (pin "2") (pinfunction "RI_2") (pintype "passive"))
    )
    (net (code "101") (name "unconnected-(U4-RTS-Pad24)") (class "Default")
      (node (ref "U4") (pin "24") (pinfunction "RTS_24") (pintype "passive"))
    )
    (net (code "102") (name "unconnected-(U4-SUSP-Pad11)") (class "Default")
      (node (ref "U4") (pin "11") (pinfunction "SUSP_11") (pintype "passive"))
    )
    (net (code "103") (name "unconnected-(U4-SUSP-Pad12)") (class "Default")
      (node (ref "U4") (pin "12") (pinfunction "SUSP_12") (pintype "passive"))
    )
  )
)
